# RS422_ADM3076.net
KiCad netlist of a schematic drawn in Altium Designer
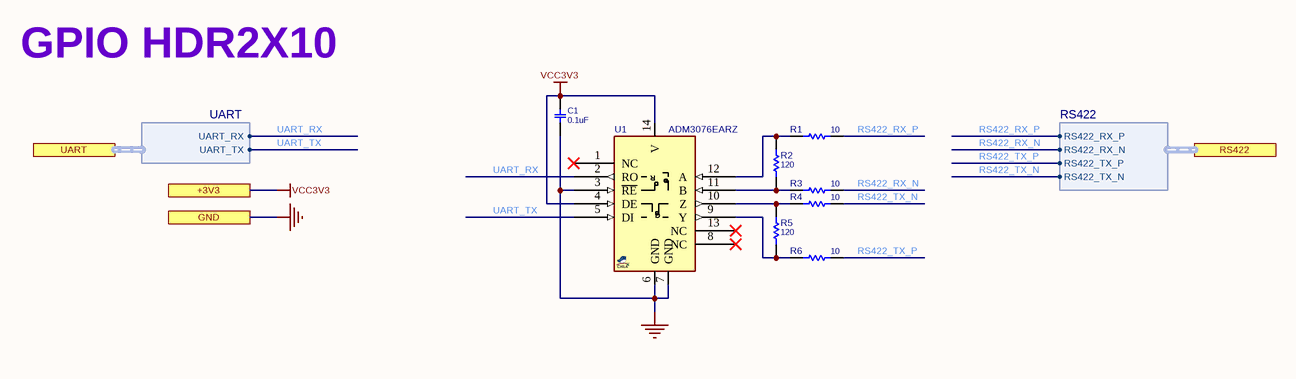
[diagram p0: RS422_ADM3076.SchDoc]

(export (version "E")
  (design (tool "Eeschema 10.0.6"))
  (components
    (comp (ref "C1")
      (value "0.1uF")
      (footprint "C0402")
      (description "CAP, MLCC, 100nF, 50V, X7R, 10%, 0402C")
      (fields (field (name "MANF_P#") "UMK105B7104KVHF") (field (name "MANF") "Taiyo Yuden"))
      (libsource (lib "mlcc_smd_passive") (part "CAP_SMD_MLCC_100n50T"))
    )
    (comp (ref "R1")
      (value "10")
      (footprint "R0402")
      (description "RESISTOR, SMD")
      (fields (field (name "MANF") "Yageo") (field (name "MANF_P#") "RC0402FR-0710RL"))
      (libsource (lib "passive_res_smd") (part "RES_SMD_10K_0402"))
    )
    (comp (ref "R2")
      (value "120")
      (footprint "R0603")
      (description "RESISTOR, SMD")
      (libsource (lib "passive_res_smd") (part "RES_SMD_10K_0402"))
    )
    (comp (ref "R3")
      (value "10")
      (footprint "R0402")
      (description "RESISTOR, SMD")
      (fields (field (name "MANF") "Yageo") (field (name "MANF_P#") "RC0402FR-0710RL"))
      (libsource (lib "passive_res_smd") (part "RES_SMD_10K_0402"))
    )
    (comp (ref "R4")
      (value "10")
      (footprint "R0402")
      (description "RESISTOR, SMD")
      (fields (field (name "MANF") "Yageo") (field (name "MANF_P#") "RC0402FR-0710RL"))
      (libsource (lib "passive_res_smd") (part "RES_SMD_10K_0402"))
    )
    (comp (ref "R5")
      (value "120")
      (footprint "R0603")
      (description "RESISTOR, SMD")
      (libsource (lib "passive_res_smd") (part "RES_SMD_10K_0402"))
    )
    (comp (ref "R6")
      (value "10")
      (footprint "R0402")
      (description "RESISTOR, SMD")
      (fields (field (name "MANF") "Yageo") (field (name "MANF_P#") "RC0402FR-0710RL"))
      (libsource (lib "passive_res_smd") (part "RES_SMD_10K_0402"))
    )
    (comp (ref "U1")
      (value "ADM3076EARZ")
      (footprint "SO_14")
      (description "RS-485/RS-422 Transceiver, FULL-DUPLEX")
      (fields (field (name "MANF") "Maxim Integrated"))
      (libsource (lib "rs485-422") (part "MAX491_SOP14"))
    )
  )
  (nets
    (net (code "3") (name "/RS422_RX_N") (class "Default")
      (node (ref "R3") (pin "2") (pinfunction "2_2") (pintype "passive"))
    )
    (net (code "4") (name "/RS422_RX_P") (class "Default")
      (node (ref "R1") (pin "2") (pinfunction "2_2") (pintype "passive"))
    )
    (net (code "5") (name "/RS422_TX_N") (class "Default")
      (node (ref "R4") (pin "2") (pinfunction "2_2") (pintype "passive"))
    )
    (net (code "6") (name "/RS422_TX_P") (class "Default")
      (node (ref "R6") (pin "2") (pinfunction "2_2") (pintype "passive"))
    )
    (net (code "7") (name "/UART_RX") (class "Default")
      (node (ref "U1") (pin "2") (pinfunction "RO_2") (pintype "output"))
    )
    (net (code "8") (name "/UART_TX") (class "Default")
      (node (ref "U1") (pin "5") (pinfunction "DI_5") (pintype "input"))
    )
    (net (code "11") (name "GND") (class "Default")
      (node (ref "C1") (pin "1") (pinfunction "1_1") (pintype "passive"))
      (node (ref "U1") (pin "3") (pinfunction "~{RE}_3") (pintype "input"))
      (node (ref "U1") (pin "6") (pinfunction "GND_6") (pintype "power_in"))
      (node (ref "U1") (pin "7") (pinfunction "GND_7") (pintype "power_in"))
    )
    (net (code "12") (name "Net-(U1-A)") (class "Default")
      (node (ref "R1") (pin "1") (pinfunction "1_1") (pintype "passive"))
      (node (ref "R2") (pin "2") (pinfunction "2_2") (pintype "passive"))
      (node (ref "U1") (pin "12") (pinfunction "A_12") (pintype "input"))
    )
    (net (code "13") (name "Net-(U1-B)") (class "Default")
      (node (ref "R2") (pin "1") (pinfunction "1_1") (pintype "passive"))
      (node (ref "R3") (pin "1") (pinfunction "1_1") (pintype "passive"))
      (node (ref "U1") (pin "11") (pinfunction "B_11") (pintype "input"))
    )
    (net (code "14") (name "Net-(U1-Y)") (class "Default")
      (node (ref "R5") (pin "1") (pinfunction "1_1") (pintype "passive"))
      (node (ref "R6") (pin "1") (pinfunction "1_1") (pintype "passive"))
      (node (ref "U1") (pin "9") (pinfunction "Y_9") (pintype "output"))
    )
    (net (code "15") (name "Net-(U1-Z)") (class "Default")
      (node (ref "R4") (pin "1") (pinfunction "1_1") (pintype "passive"))
      (node (ref "R5") (pin "2") (pinfunction "2_2") (pintype "passive"))
      (node (ref "U1") (pin "10") (pinfunction "Z_10") (pintype "output"))
    )
    (net (code "16") (name "VCC3V3") (class "Default")
      (node (ref "C1") (pin "2") (pinfunction "2_2") (pintype "passive"))
      (node (ref "U1") (pin "14") (pinfunction "V_14") (pintype "power_in"))
      (node (ref "U1") (pin "4") (pinfunction "DE_4") (pintype "input"))
    )
    (net (code "17") (name "unconnected-(U1-NC-Pad1)") (class "Default")
      (node (ref "U1") (pin "1") (pinfunction "NC_1") (pintype "passive+no_connect"))
    )
    (net (code "18") (name "unconnected-(U1-NC-Pad8)") (class "Default")
      (node (ref "U1") (pin "8") (pinfunction "NC_8") (pintype "passive+no_connect"))
    )
    (net (code "19") (name "unconnected-(U1-NC-Pad13)") (class "Default")
      (node (ref "U1") (pin "13") (pinfunction "NC_13") (pintype "passive+no_connect"))
    )
  )
)
